# stamp-fixed-mk3.net
KiCad netlist of a schematic drawn in EAGLE
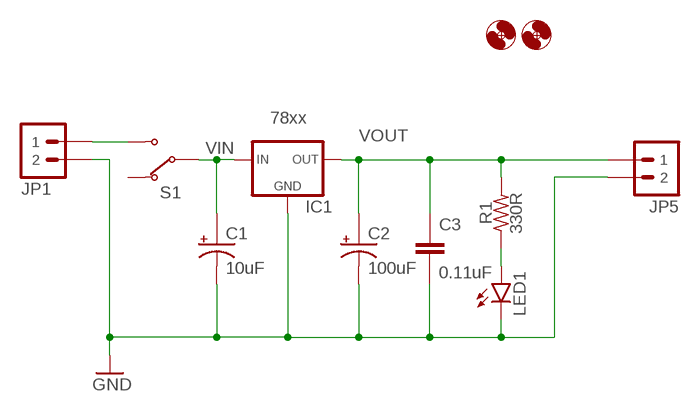
[diagram p0: schematic, sheet 1]

(export (version "E")
  (design (tool "Eeschema 10.0.6"))
  (components
    (comp (ref "C1")
      (value "10uF")
      (footprint "eagle-import:E2,5-6")
      (libsource (lib "eagle-import") (part "CAPACITOR-POLARIZEDE2.5-6"))
    )
    (comp (ref "C2")
      (value "100uF")
      (footprint "eagle-import:E2,5-6")
      (libsource (lib "eagle-import") (part "CAPACITOR-POLARIZEDE2.5-6"))
    )
    (comp (ref "C3")
      (value "0.11uF")
      (footprint "eagle-import:C025-024X044")
      (libsource (lib "eagle-import") (part "CAPACITOR-CERAMIC025-024X044"))
    )
    (comp (ref "H1")
      (value "HOLE#2")
      (footprint "eagle-import:HOLE-#2")
      (libsource (lib "eagle-import") (part "HOLE#2"))
    )
    (comp (ref "H2")
      (value "HOLE#2")
      (footprint "eagle-import:HOLE-#2")
      (libsource (lib "eagle-import") (part "HOLE#2"))
    )
    (comp (ref "IC1")
      (value "78xx")
      (footprint "eagle-import:TO-220-SIDE-THERM")
      (libsource (lib "eagle-import") (part "V_REG_78XXTO-220-THERM"))
    )
    (comp (ref "JP1")
      (value "M02JST-PTH-RA-SMALLPADS")
      (footprint "eagle-import:JST-2-PH-RA-PTH-SMALLPADS")
      (libsource (lib "eagle-import") (part "M02JST-PTH-RA-SMALLPADS"))
    )
    (comp (ref "JP5")
      (value "M02JST-PTH-RA-SMALLPADS")
      (footprint "eagle-import:JST-2-PH-RA-PTH-SMALLPADS")
      (libsource (lib "eagle-import") (part "M02JST-PTH-RA-SMALLPADS"))
    )
    (comp (ref "LED1")
      (value "LED3MM")
      (footprint "eagle-import:LED3MM")
      (libsource (lib "eagle-import") (part "LED3MM"))
    )
    (comp (ref "R1")
      (value "330R")
      (footprint "eagle-import:RESISTOR-AXIAL-PTH-5.08MM")
      (libsource (lib "eagle-import") (part "RESISTORPTH-AXIAL-5.08MM"))
    )
    (comp (ref "S1")
      (value "SWITCH-SPDTPTH-VERT-2.54MM")
      (footprint "eagle-import:SWITCH-SPDT")
      (libsource (lib "eagle-import") (part "SWITCH-SPDTPTH-VERT-2.54MM"))
    )
  )
  (nets
    (net (code "1") (name "/VIN") (class "Default")
      (node (ref "C1") (pin "+") (pinfunction "+_+") (pintype "passive"))
      (node (ref "IC1") (pin "IN") (pinfunction "IN_IN") (pintype "input"))
      (node (ref "S1") (pin "2") (pinfunction "COM_2") (pintype "passive"))
    )
    (net (code "2") (name "/VOUT") (class "Default")
      (node (ref "C2") (pin "+") (pinfunction "+_+") (pintype "passive"))
      (node (ref "C3") (pin "1") (pinfunction "1_1") (pintype "passive"))
      (node (ref "IC1") (pin "OUT") (pinfunction "OUT_OUT") (pintype "output"))
      (node (ref "JP5") (pin "1") (pinfunction "1_1") (pintype "passive"))
      (node (ref "R1") (pin "P$2") (pinfunction "2_P$2") (pintype "passive"))
    )
    (net (code "3") (name "GND") (class "Default")
      (node (ref "C1") (pin "-") (pinfunction "-_-") (pintype "passive"))
      (node (ref "C2") (pin "-") (pinfunction "-_-") (pintype "passive"))
      (node (ref "C3") (pin "2") (pinfunction "2_2") (pintype "passive"))
      (node (ref "IC1") (pin "GND") (pinfunction "GND_GND") (pintype "input"))
      (node (ref "IC1") (pin "GND@1") (pinfunction "GND_GND@1") (pintype "input"))
      (node (ref "IC1") (pin "GND@10") (pinfunction "GND_GND@10") (pintype "input"))
      (node (ref "IC1") (pin "GND@11") (pinfunction "GND_GND@11") (pintype "input"))
      (node (ref "IC1") (pin "GND@12") (pinfunction "GND_GND@12") (pintype "input"))
      (node (ref "IC1") (pin "GND@13") (pinfunction "GND_GND@13") (pintype "input"))
      (node (ref "IC1") (pin "GND@14") (pinfunction "GND_GND@14") (pintype "input"))
      (node (ref "IC1") (pin "GND@15") (pinfunction "GND_GND@15") (pintype "input"))
      (node (ref "IC1") (pin "GND@16") (pinfunction "GND_GND@16") (pintype "input"))
      (node (ref "IC1") (pin "GND@17") (pinfunction "GND_GND@17") (pintype "input"))
      (node (ref "IC1") (pin "GND@18") (pinfunction "GND_GND@18") (pintype "input"))
      (node (ref "IC1") (pin "GND@19") (pinfunction "GND_GND@19") (pintype "input"))
      (node (ref "IC1") (pin "GND@2") (pinfunction "GND_GND@2") (pintype "input"))
      (node (ref "IC1") (pin "GND@20") (pinfunction "GND_GND@20") (pintype "input"))
      (node (ref "IC1") (pin "GND@21") (pinfunction "GND_GND@21") (pintype "input"))
      (node (ref "IC1") (pin "GND@22") (pinfunction "GND_GND@22") (pintype "input"))
      (node (ref "IC1") (pin "GND@23") (pinfunction "GND_GND@23") (pintype "input"))
      (node (ref "IC1") (pin "GND@24") (pinfunction "GND_GND@24") (pintype "input"))
      (node (ref "IC1") (pin "GND@25") (pinfunction "GND_GND@25") (pintype "input"))
      (node (ref "IC1") (pin "GND@26") (pinfunction "GND_GND@26") (pintype "input"))
      (node (ref "IC1") (pin "GND@27") (pinfunction "GND_GND@27") (pintype "input"))
      (node (ref "IC1") (pin "GND@3") (pinfunction "GND_GND@3") (pintype "input"))
      (node (ref "IC1") (pin "GND@4") (pinfunction "GND_GND@4") (pintype "input"))
      (node (ref "IC1") (pin "GND@5") (pinfunction "GND_GND@5") (pintype "input"))
      (node (ref "IC1") (pin "GND@6") (pinfunction "GND_GND@6") (pintype "input"))
      (node (ref "IC1") (pin "GND@7") (pinfunction "GND_GND@7") (pintype "input"))
      (node (ref "IC1") (pin "GND@8") (pinfunction "GND_GND@8") (pintype "input"))
      (node (ref "IC1") (pin "GND@9") (pinfunction "GND_GND@9") (pintype "input"))
      (node (ref "JP1") (pin "2") (pinfunction "2_2") (pintype "passive"))
      (node (ref "JP5") (pin "2") (pinfunction "2_2") (pintype "passive"))
      (node (ref "LED1") (pin "K") (pinfunction "C_K") (pintype "passive"))
    )
    (net (code "4") (name "Net-(R1-1)") (class "Default")
      (node (ref "LED1") (pin "A") (pinfunction "A_A") (pintype "passive"))
      (node (ref "R1") (pin "P$1") (pinfunction "1_P$1") (pintype "passive"))
    )
    (net (code "5") (name "Net-(S1-NO)") (class "Default")
      (node (ref "JP1") (pin "1") (pinfunction "1_1") (pintype "passive"))
      (node (ref "S1") (pin "3") (pinfunction "NO_3") (pintype "passive"))
    )
    (net (code "6") (name "unconnected-(S1-NC-Pad1)") (class "Default")
      (node (ref "S1") (pin "1") (pinfunction "NC_1") (pintype "passive"))
    )
  )
)
